# data_board.net
KiCad netlist of a schematic drawn in EAGLE
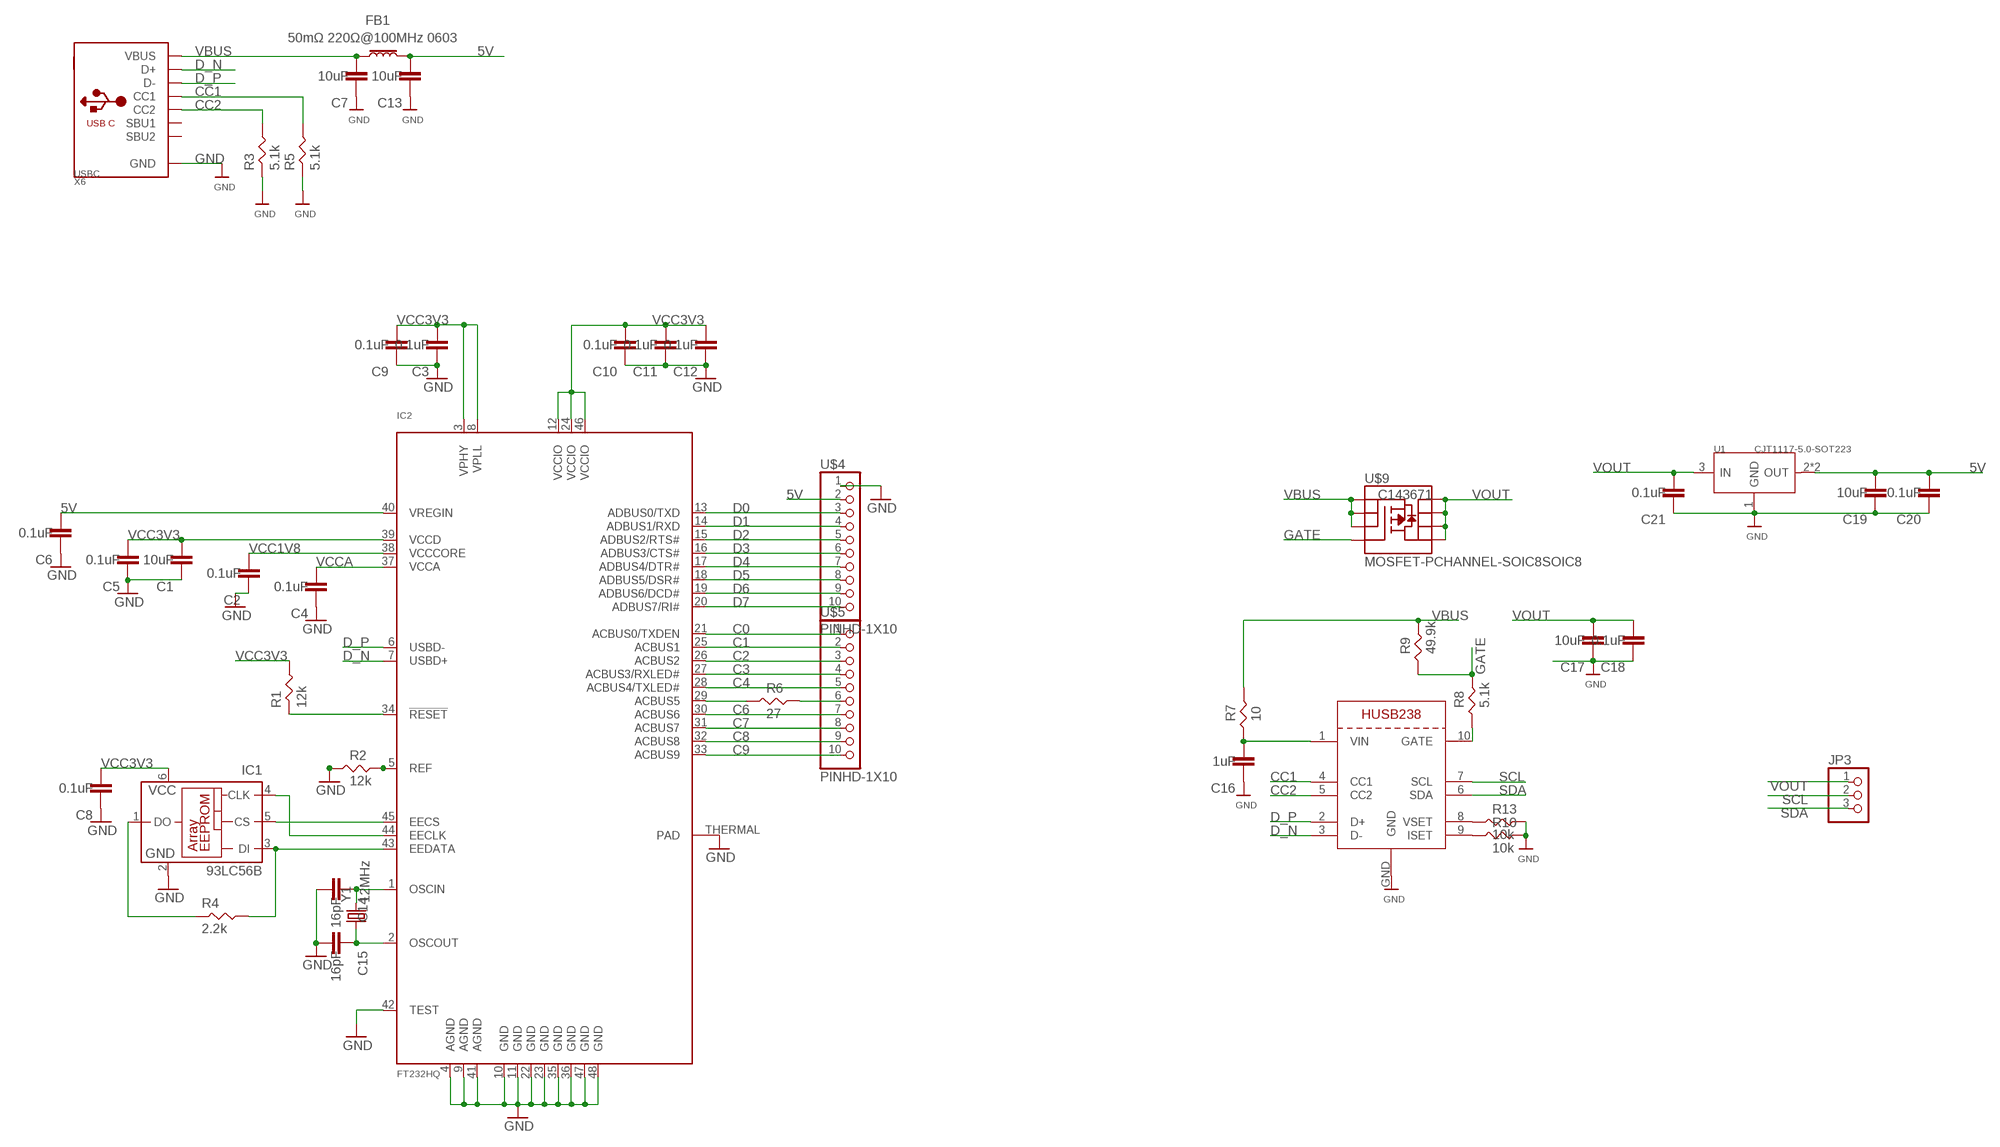
[diagram p0: schematic, sheet 1]

(export (version "E")
  (design (tool "Eeschema 10.0.6"))
  (components
    (comp (ref "C1")
      (value "10uF")
      (footprint "eagle-import:RESC0805_N")
      (libsource (lib "eagle-import") (part "CAPACITOR_0805_N"))
    )
    (comp (ref "C2")
      (value "0.1uF")
      (footprint "eagle-import:RESC0402_N")
      (libsource (lib "eagle-import") (part "CAPACITOR_0402_N"))
    )
    (comp (ref "C3")
      (value "0.1uF")
      (footprint "eagle-import:RESC0402_N")
      (libsource (lib "eagle-import") (part "CAPACITOR_0402_N"))
    )
    (comp (ref "C4")
      (value "0.1uF")
      (footprint "eagle-import:RESC0402_N")
      (libsource (lib "eagle-import") (part "CAPACITOR_0402_N"))
    )
    (comp (ref "C5")
      (value "0.1uF")
      (footprint "eagle-import:RESC0402_N")
      (libsource (lib "eagle-import") (part "CAPACITOR_0402_N"))
    )
    (comp (ref "C6")
      (value "0.1uF")
      (footprint "eagle-import:RESC0402_N")
      (libsource (lib "eagle-import") (part "CAPACITOR_0402_N"))
    )
    (comp (ref "C7")
      (value "10uF")
      (footprint "eagle-import:RESC0805_N")
      (libsource (lib "eagle-import") (part "CAPACITOR_0805_N"))
    )
    (comp (ref "C8")
      (value "0.1uF")
      (footprint "eagle-import:RESC0402_N")
      (libsource (lib "eagle-import") (part "CAPACITOR_0402_N"))
    )
    (comp (ref "C9")
      (value "0.1uF")
      (footprint "eagle-import:RESC0402_N")
      (libsource (lib "eagle-import") (part "CAPACITOR_0402_N"))
    )
    (comp (ref "C10")
      (value "0.1uF")
      (footprint "eagle-import:RESC0402_N")
      (libsource (lib "eagle-import") (part "CAPACITOR_0402_N"))
    )
    (comp (ref "C11")
      (value "0.1uF")
      (footprint "eagle-import:RESC0402_N")
      (libsource (lib "eagle-import") (part "CAPACITOR_0402_N"))
    )
    (comp (ref "C12")
      (value "0.1uF")
      (footprint "eagle-import:RESC0402_N")
      (libsource (lib "eagle-import") (part "CAPACITOR_0402_N"))
    )
    (comp (ref "C13")
      (value "10uF")
      (footprint "eagle-import:RESC0805_N")
      (libsource (lib "eagle-import") (part "CAPACITOR_0805_N"))
    )
    (comp (ref "C14")
      (value "16pF")
      (footprint "eagle-import:RESC0402_N")
      (libsource (lib "eagle-import") (part "CAPACITOR_0402_N"))
    )
    (comp (ref "C15")
      (value "16pF")
      (footprint "eagle-import:RESC0402_N")
      (libsource (lib "eagle-import") (part "CAPACITOR_0402_N"))
    )
    (comp (ref "C16")
      (value "1uF")
      (footprint "eagle-import:RESC0402_N")
      (libsource (lib "eagle-import") (part "CAPACITOR_0402_N"))
    )
    (comp (ref "C17")
      (value "10uF")
      (footprint "eagle-import:RESC0805_N")
      (libsource (lib "eagle-import") (part "CAPACITOR_0805_N"))
    )
    (comp (ref "C18")
      (value "0.1uF")
      (footprint "eagle-import:RESC0402_N")
      (libsource (lib "eagle-import") (part "CAPACITOR_0402_N"))
    )
    (comp (ref "C19")
      (value "10uF")
      (footprint "eagle-import:RESC0805_N")
      (libsource (lib "eagle-import") (part "CAPACITOR_0805_N"))
    )
    (comp (ref "C20")
      (value "0.1uF")
      (footprint "eagle-import:RESC0402_N")
      (libsource (lib "eagle-import") (part "CAPACITOR_0402_N"))
    )
    (comp (ref "C21")
      (value "0.1uF")
      (footprint "eagle-import:RESC0402_N")
      (libsource (lib "eagle-import") (part "CAPACITOR_0402_N"))
    )
    (comp (ref "FB1")
      (value "50mΩ 220Ω@100MHz 0603")
      (footprint "eagle-import:0603")
      (libsource (lib "eagle-import") (part "FERRITE_BEAD-0603"))
    )
    (comp (ref "IC1")
      (value "93LC56B")
      (footprint "eagle-import:SOT23-6")
      (fields (field (name "MF") "MICROCHIP") (field (name "MPN") "93LC76AT-I/OT"))
      (libsource (lib "eagle-import") (part "9376?ALC"))
    )
    (comp (ref "IC2")
      (value "FT232HQ")
      (footprint "eagle-import:QFN48_8MM")
      (libsource (lib "eagle-import") (part "FT232HQ"))
    )
    (comp (ref "JP3")
      (value "HEADER-1X3ROUND")
      (footprint "eagle-import:1X03_ROUND")
      (libsource (lib "eagle-import") (part "HEADER-1X3ROUND"))
    )
    (comp (ref "R1")
      (value "12k")
      (footprint "eagle-import:RES-0402")
      (libsource (lib "eagle-import") (part "RES-0402"))
    )
    (comp (ref "R2")
      (value "12k")
      (footprint "eagle-import:RES-0402")
      (libsource (lib "eagle-import") (part "RES-0402"))
    )
    (comp (ref "R3")
      (value "5.1k")
      (footprint "eagle-import:RES-0402")
      (libsource (lib "eagle-import") (part "RES-0402"))
    )
    (comp (ref "R4")
      (value "2.2k")
      (footprint "eagle-import:RES-0402")
      (libsource (lib "eagle-import") (part "RES-0402"))
    )
    (comp (ref "R5")
      (value "5.1k")
      (footprint "eagle-import:RES-0402")
      (libsource (lib "eagle-import") (part "RES-0402"))
    )
    (comp (ref "R6")
      (value "27")
      (footprint "eagle-import:RES-0402")
      (libsource (lib "eagle-import") (part "RES-0402"))
    )
    (comp (ref "R7")
      (value "10")
      (footprint "eagle-import:RES-0402")
      (libsource (lib "eagle-import") (part "RES-0402"))
    )
    (comp (ref "R8")
      (value "5.1k")
      (footprint "eagle-import:RES-0402")
      (libsource (lib "eagle-import") (part "RES-0402"))
    )
    (comp (ref "R9")
      (value "49.9k")
      (footprint "eagle-import:RES-0402")
      (libsource (lib "eagle-import") (part "RES-0402"))
    )
    (comp (ref "R10")
      (value "10k")
      (footprint "eagle-import:RES-0402")
      (libsource (lib "eagle-import") (part "RES-0402"))
    )
    (comp (ref "R13")
      (value "10k")
      (footprint "eagle-import:RES-0402")
      (libsource (lib "eagle-import") (part "RES-0402"))
    )
    (comp (ref "U$4")
      (value "PINHD-1X10")
      (footprint "eagle-import:1X10-BIG")
      (libsource (lib "eagle-import") (part "PINHD-1X10"))
    )
    (comp (ref "U$5")
      (value "PINHD-1X10")
      (footprint "eagle-import:1X10-BIG")
      (libsource (lib "eagle-import") (part "PINHD-1X10"))
    )
    (comp (ref "U$9")
      (value "MOSFET-PCHANNEL-SOIC8SOIC8")
      (footprint "eagle-import:SO08")
      (fields (field (name "LCSC") "C143671"))
      (libsource (lib "eagle-import") (part "MOSFET-PCHANNEL-SOIC8SOIC8"))
    )
    (comp (ref "U1")
      (value "CJT1117-5.0-SOT223")
      (footprint "eagle-import:SOT-223")
      (fields (field (name "MPN") "CJT1117-5.0"))
      (libsource (lib "eagle-import") (part "PMIC-CJT1117-5.0(SOT223)"))
    )
    (comp (ref "X3")
      (value "HUSB238")
      (footprint "eagle-import:DFN10_3X3MM")
      (libsource (lib "eagle-import") (part "HUSB238"))
    )
    (comp (ref "X6")
      (value "USBC")
      (footprint "eagle-import:USB_C_CUSB31-CFM2AX-01-X")
      (libsource (lib "eagle-import") (part "USB_C"))
    )
    (comp (ref "Y1")
      (value "12MHz")
      (footprint "eagle-import:CRYSTAL-SMD-5X3")
      (libsource (lib "eagle-import") (part "CRYSTALCRYSTAL-SMD-5X3-12MHZ"))
    )
  )
  (nets
    (net (code "1") (name "/5V") (class "Default")
      (node (ref "C13") (pin "2") (pinfunction "2_2") (pintype "passive"))
      (node (ref "C19") (pin "2") (pinfunction "2_2") (pintype "passive"))
      (node (ref "C20") (pin "2") (pinfunction "2_2") (pintype "passive"))
      (node (ref "C6") (pin "2") (pinfunction "2_2") (pintype "passive"))
      (node (ref "FB1") (pin "2") (pinfunction "2_2") (pintype "passive"))
      (node (ref "IC2") (pin "40") (pinfunction "VREGIN_40") (pintype "power_in"))
      (node (ref "U$4") (pin "2") (pinfunction "2_2") (pintype "passive"))
      (node (ref "U1") (pin "2") (pinfunction "OUT_2") (pintype "bidirectional"))
      (node (ref "U1") (pin "TER") (pinfunction "OUT_TER") (pintype "bidirectional"))
    )
    (net (code "2") (name "/C0") (class "Default")
      (node (ref "IC2") (pin "21") (pinfunction "ACBUS0/TXDEN_21") (pintype "bidirectional"))
      (node (ref "U$5") (pin "1") (pinfunction "1_1") (pintype "passive"))
    )
    (net (code "3") (name "/C1") (class "Default")
      (node (ref "IC2") (pin "25") (pinfunction "ACBUS1_25") (pintype "bidirectional"))
      (node (ref "U$5") (pin "2") (pinfunction "2_2") (pintype "passive"))
    )
    (net (code "4") (name "/C2") (class "Default")
      (node (ref "IC2") (pin "26") (pinfunction "ACBUS2_26") (pintype "bidirectional"))
      (node (ref "U$5") (pin "3") (pinfunction "3_3") (pintype "passive"))
    )
    (net (code "5") (name "/C3") (class "Default")
      (node (ref "IC2") (pin "27") (pinfunction "ACBUS3/RXLED#_27") (pintype "bidirectional"))
      (node (ref "U$5") (pin "4") (pinfunction "4_4") (pintype "passive"))
    )
    (net (code "6") (name "/C4") (class "Default")
      (node (ref "IC2") (pin "28") (pinfunction "ACBUS4/TXLED#_28") (pintype "bidirectional"))
      (node (ref "U$5") (pin "5") (pinfunction "5_5") (pintype "passive"))
    )
    (net (code "7") (name "/C6") (class "Default")
      (node (ref "IC2") (pin "30") (pinfunction "ACBUS6_30") (pintype "bidirectional"))
      (node (ref "U$5") (pin "7") (pinfunction "7_7") (pintype "passive"))
    )
    (net (code "8") (name "/C7") (class "Default")
      (node (ref "IC2") (pin "31") (pinfunction "ACBUS7_31") (pintype "bidirectional"))
      (node (ref "U$5") (pin "8") (pinfunction "8_8") (pintype "passive"))
    )
    (net (code "9") (name "/C8") (class "Default")
      (node (ref "IC2") (pin "32") (pinfunction "ACBUS8_32") (pintype "bidirectional"))
      (node (ref "U$5") (pin "9") (pinfunction "9_9") (pintype "passive"))
    )
    (net (code "10") (name "/C9") (class "Default")
      (node (ref "IC2") (pin "33") (pinfunction "ACBUS9_33") (pintype "bidirectional"))
      (node (ref "U$5") (pin "10") (pinfunction "10_10") (pintype "passive"))
    )
    (net (code "11") (name "/CC1") (class "Default")
      (node (ref "R5") (pin "P$2") (pinfunction "P$2_P$2") (pintype "bidirectional"))
      (node (ref "X3") (pin "4") (pinfunction "CC1_4") (pintype "input"))
      (node (ref "X6") (pin "A5") (pinfunction "CC1_A5") (pintype "bidirectional"))
    )
    (net (code "12") (name "/CC2") (class "Default")
      (node (ref "R3") (pin "P$2") (pinfunction "P$2_P$2") (pintype "bidirectional"))
      (node (ref "X3") (pin "5") (pinfunction "CC2_5") (pintype "input"))
      (node (ref "X6") (pin "B5") (pinfunction "CC2_B5") (pintype "bidirectional"))
    )
    (net (code "13") (name "/D0") (class "Default")
      (node (ref "IC2") (pin "13") (pinfunction "ADBUS0/TXD_13") (pintype "output"))
      (node (ref "U$4") (pin "3") (pinfunction "3_3") (pintype "passive"))
    )
    (net (code "14") (name "/D1") (class "Default")
      (node (ref "IC2") (pin "14") (pinfunction "ADBUS1/RXD_14") (pintype "input"))
      (node (ref "U$4") (pin "4") (pinfunction "4_4") (pintype "passive"))
    )
    (net (code "15") (name "/D2") (class "Default")
      (node (ref "IC2") (pin "15") (pinfunction "ADBUS2/RTS#_15") (pintype "output"))
      (node (ref "U$4") (pin "5") (pinfunction "5_5") (pintype "passive"))
    )
    (net (code "16") (name "/D3") (class "Default")
      (node (ref "IC2") (pin "16") (pinfunction "ADBUS3/CTS#_16") (pintype "input"))
      (node (ref "U$4") (pin "6") (pinfunction "6_6") (pintype "passive"))
    )
    (net (code "17") (name "/D4") (class "Default")
      (node (ref "IC2") (pin "17") (pinfunction "ADBUS4/DTR#_17") (pintype "output"))
      (node (ref "U$4") (pin "7") (pinfunction "7_7") (pintype "passive"))
    )
    (net (code "18") (name "/D5") (class "Default")
      (node (ref "IC2") (pin "18") (pinfunction "ADBUS5/DSR#_18") (pintype "input"))
      (node (ref "U$4") (pin "8") (pinfunction "8_8") (pintype "passive"))
    )
    (net (code "19") (name "/D6") (class "Default")
      (node (ref "IC2") (pin "19") (pinfunction "ADBUS6/DCD#_19") (pintype "input"))
      (node (ref "U$4") (pin "9") (pinfunction "9_9") (pintype "passive"))
    )
    (net (code "20") (name "/D7") (class "Default")
      (node (ref "IC2") (pin "20") (pinfunction "ADBUS7/RI#_20") (pintype "input"))
      (node (ref "U$4") (pin "10") (pinfunction "10_10") (pintype "passive"))
    )
    (net (code "21") (name "/D_N") (class "Default")
      (node (ref "IC2") (pin "7") (pinfunction "USBD+_7") (pintype "bidirectional"))
      (node (ref "X3") (pin "3") (pinfunction "D-_3") (pintype "input"))
      (node (ref "X6") (pin "A6") (pinfunction "D+_A6") (pintype "bidirectional"))
      (node (ref "X6") (pin "B6") (pinfunction "D+_B6") (pintype "bidirectional"))
    )
    (net (code "22") (name "/D_P") (class "Default")
      (node (ref "IC2") (pin "6") (pinfunction "USBD-_6") (pintype "bidirectional"))
      (node (ref "X3") (pin "2") (pinfunction "D+_2") (pintype "input"))
      (node (ref "X6") (pin "A7") (pinfunction "D-_A7") (pintype "bidirectional"))
      (node (ref "X6") (pin "B7") (pinfunction "D-_B7") (pintype "bidirectional"))
    )
    (net (code "23") (name "/GATE") (class "Default")
      (node (ref "R8") (pin "P$2") (pinfunction "P$2_P$2") (pintype "bidirectional"))
      (node (ref "R9") (pin "P$1") (pinfunction "P$1_P$1") (pintype "bidirectional"))
      (node (ref "U$9") (pin "4") (pinfunction "G_4") (pintype "bidirectional"))
    )
    (net (code "24") (name "/SCL") (class "Default")
      (node (ref "JP3") (pin "2") (pinfunction "2_2") (pintype "passive"))
      (node (ref "X3") (pin "7") (pinfunction "SCL_7") (pintype "bidirectional"))
    )
    (net (code "25") (name "/SDA") (class "Default")
      (node (ref "JP3") (pin "3") (pinfunction "3_3") (pintype "passive"))
      (node (ref "X3") (pin "6") (pinfunction "SDA_6") (pintype "bidirectional"))
    )
    (net (code "26") (name "/VBUS") (class "Default")
      (node (ref "C7") (pin "2") (pinfunction "2_2") (pintype "passive"))
      (node (ref "FB1") (pin "1") (pinfunction "1_1") (pintype "passive"))
      (node (ref "R7") (pin "P$2") (pinfunction "P$2_P$2") (pintype "bidirectional"))
      (node (ref "R9") (pin "P$2") (pinfunction "P$2_P$2") (pintype "bidirectional"))
      (node (ref "U$9") (pin "1") (pinfunction "S_1") (pintype "bidirectional"))
      (node (ref "U$9") (pin "2") (pinfunction "S_2") (pintype "bidirectional"))
      (node (ref "U$9") (pin "3") (pinfunction "S_3") (pintype "bidirectional"))
      (node (ref "X6") (pin "A4B9") (pinfunction "VBUS_A4B9") (pintype "power_in"))
      (node (ref "X6") (pin "B4A9") (pinfunction "VBUS_B4A9") (pintype "power_in"))
    )
    (net (code "27") (name "/VCC1V8") (class "Default")
      (node (ref "C2") (pin "2") (pinfunction "2_2") (pintype "passive"))
      (node (ref "IC2") (pin "38") (pinfunction "VCCCORE_38") (pintype "power_in"))
    )
    (net (code "28") (name "/VCC3V3") (class "Default")
      (node (ref "C1") (pin "2") (pinfunction "2_2") (pintype "passive"))
      (node (ref "C10") (pin "2") (pinfunction "2_2") (pintype "passive"))
      (node (ref "C11") (pin "2") (pinfunction "2_2") (pintype "passive"))
      (node (ref "C12") (pin "2") (pinfunction "2_2") (pintype "passive"))
      (node (ref "C3") (pin "2") (pinfunction "2_2") (pintype "passive"))
      (node (ref "C5") (pin "2") (pinfunction "2_2") (pintype "passive"))
      (node (ref "C8") (pin "2") (pinfunction "2_2") (pintype "passive"))
      (node (ref "C9") (pin "2") (pinfunction "2_2") (pintype "passive"))
      (node (ref "IC1") (pin "6") (pinfunction "VCC_6") (pintype "power_in"))
      (node (ref "IC2") (pin "12") (pinfunction "VCCIO_12") (pintype "power_in"))
      (node (ref "IC2") (pin "24") (pinfunction "VCCIO_24") (pintype "power_in"))
      (node (ref "IC2") (pin "3") (pinfunction "VPHY_3") (pintype "power_in"))
      (node (ref "IC2") (pin "39") (pinfunction "VCCD_39") (pintype "power_in"))
      (node (ref "IC2") (pin "46") (pinfunction "VCCIO_46") (pintype "power_in"))
      (node (ref "IC2") (pin "8") (pinfunction "VPLL_8") (pintype "power_in"))
      (node (ref "R1") (pin "P$2") (pinfunction "P$2_P$2") (pintype "bidirectional"))
    )
    (net (code "29") (name "/VCCA") (class "Default")
      (node (ref "C4") (pin "2") (pinfunction "2_2") (pintype "passive"))
      (node (ref "IC2") (pin "37") (pinfunction "VCCA_37") (pintype "power_in"))
    )
    (net (code "30") (name "/VOUT") (class "Default")
      (node (ref "C17") (pin "2") (pinfunction "2_2") (pintype "passive"))
      (node (ref "C18") (pin "2") (pinfunction "2_2") (pintype "passive"))
      (node (ref "C21") (pin "2") (pinfunction "2_2") (pintype "passive"))
      (node (ref "JP3") (pin "1") (pinfunction "1_1") (pintype "passive"))
      (node (ref "U$9") (pin "5") (pinfunction "D_5") (pintype "bidirectional"))
      (node (ref "U$9") (pin "6") (pinfunction "D_6") (pintype "bidirectional"))
      (node (ref "U$9") (pin "7") (pinfunction "D_7") (pintype "bidirectional"))
      (node (ref "U$9") (pin "8") (pinfunction "D_8") (pintype "bidirectional"))
      (node (ref "U1") (pin "3") (pinfunction "IN_3") (pintype "bidirectional"))
    )
    (net (code "31") (name "GND") (class "Default")
      (node (ref "C1") (pin "1") (pinfunction "1_1") (pintype "passive"))
      (node (ref "C10") (pin "1") (pinfunction "1_1") (pintype "passive"))
      (node (ref "C11") (pin "1") (pinfunction "1_1") (pintype "passive"))
      (node (ref "C12") (pin "1") (pinfunction "1_1") (pintype "passive"))
      (node (ref "C13") (pin "1") (pinfunction "1_1") (pintype "passive"))
      (node (ref "C14") (pin "2") (pinfunction "2_2") (pintype "passive"))
      (node (ref "C15") (pin "2") (pinfunction "2_2") (pintype "passive"))
      (node (ref "C16") (pin "1") (pinfunction "1_1") (pintype "passive"))
      (node (ref "C17") (pin "1") (pinfunction "1_1") (pintype "passive"))
      (node (ref "C18") (pin "1") (pinfunction "1_1") (pintype "passive"))
      (node (ref "C19") (pin "1") (pinfunction "1_1") (pintype "passive"))
      (node (ref "C2") (pin "1") (pinfunction "1_1") (pintype "passive"))
      (node (ref "C20") (pin "1") (pinfunction "1_1") (pintype "passive"))
      (node (ref "C21") (pin "1") (pinfunction "1_1") (pintype "passive"))
      (node (ref "C3") (pin "1") (pinfunction "1_1") (pintype "passive"))
      (node (ref "C4") (pin "1") (pinfunction "1_1") (pintype "passive"))
      (node (ref "C5") (pin "1") (pinfunction "1_1") (pintype "passive"))
      (node (ref "C6") (pin "1") (pinfunction "1_1") (pintype "passive"))
      (node (ref "C7") (pin "1") (pinfunction "1_1") (pintype "passive"))
      (node (ref "C8") (pin "1") (pinfunction "1_1") (pintype "passive"))
      (node (ref "C9") (pin "1") (pinfunction "1_1") (pintype "passive"))
      (node (ref "IC1") (pin "2") (pinfunction "GND_2") (pintype "power_in"))
      (node (ref "IC2") (pin "10") (pinfunction "GND_10") (pintype "power_in"))
      (node (ref "IC2") (pin "11") (pinfunction "GND_11") (pintype "power_in"))
      (node (ref "IC2") (pin "22") (pinfunction "GND_22") (pintype "power_in"))
      (node (ref "IC2") (pin "23") (pinfunction "GND_23") (pintype "power_in"))
      (node (ref "IC2") (pin "35") (pinfunction "GND_35") (pintype "power_in"))
      (node (ref "IC2") (pin "36") (pinfunction "GND_36") (pintype "power_in"))
      (node (ref "IC2") (pin "4") (pinfunction "AGND_4") (pintype "power_in"))
      (node (ref "IC2") (pin "41") (pinfunction "AGND_41") (pintype "power_in"))
      (node (ref "IC2") (pin "42") (pinfunction "TEST_42") (pintype "input"))
      (node (ref "IC2") (pin "47") (pinfunction "GND_47") (pintype "power_in"))
      (node (ref "IC2") (pin "48") (pinfunction "GND_48") (pintype "power_in"))
      (node (ref "IC2") (pin "9") (pinfunction "AGND_9") (pintype "power_in"))
      (node (ref "IC2") (pin "THERMAL") (pinfunction "PAD_THERMAL") (pintype "passive"))
      (node (ref "R10") (pin "P$2") (pinfunction "P$2_P$2") (pintype "bidirectional"))
      (node (ref "R13") (pin "P$2") (pinfunction "P$2_P$2") (pintype "bidirectional"))
      (node (ref "R2") (pin "P$1") (pinfunction "P$1_P$1") (pintype "bidirectional"))
      (node (ref "R3") (pin "P$1") (pinfunction "P$1_P$1") (pintype "bidirectional"))
      (node (ref "R5") (pin "P$1") (pinfunction "P$1_P$1") (pintype "bidirectional"))
      (node (ref "U$4") (pin "1") (pinfunction "1_1") (pintype "passive"))
      (node (ref "U1") (pin "1") (pinfunction "GND_1") (pintype "bidirectional"))
      (node (ref "X3") (pin "GND") (pinfunction "GND_GND") (pintype "power_in"))
      (node (ref "X6") (pin "A1B12") (pinfunction "GND_A1B12") (pintype "power_in"))
      (node (ref "X6") (pin "B1A12") (pinfunction "GND_B1A12") (pintype "power_in"))
    )
    (net (code "32") (name "Net-(IC1-CLK)") (class "Default")
      (node (ref "IC1") (pin "4") (pinfunction "CLK_4") (pintype "input"))
      (node (ref "IC2") (pin "44") (pinfunction "EECLK_44") (pintype "output"))
    )
    (net (code "33") (name "Net-(IC1-CS)") (class "Default")
      (node (ref "IC1") (pin "5") (pinfunction "CS_5") (pintype "input"))
      (node (ref "IC2") (pin "45") (pinfunction "EECS_45") (pintype "bidirectional"))
    )
    (net (code "34") (name "Net-(IC1-DI)") (class "Default")
      (node (ref "IC1") (pin "3") (pinfunction "DI_3") (pintype "input"))
      (node (ref "IC2") (pin "43") (pinfunction "EEDATA_43") (pintype "bidirectional"))
      (node (ref "R4") (pin "P$2") (pinfunction "P$2_P$2") (pintype "bidirectional"))
    )
    (net (code "35") (name "Net-(IC1-DO)") (class "Default")
      (node (ref "IC1") (pin "1") (pinfunction "DO_1") (pintype "tri_state"))
      (node (ref "R4") (pin "P$1") (pinfunction "P$1_P$1") (pintype "bidirectional"))
    )
    (net (code "36") (name "Net-(IC2-ACBUS5)") (class "Default")
      (node (ref "IC2") (pin "29") (pinfunction "ACBUS5_29") (pintype "bidirectional"))
      (node (ref "R6") (pin "P$1") (pinfunction "P$1_P$1") (pintype "bidirectional"))
    )
    (net (code "37") (name "Net-(IC2-OSCIN)") (class "Default")
      (node (ref "C14") (pin "1") (pinfunction "1_1") (pintype "passive"))
      (node (ref "IC2") (pin "1") (pinfunction "OSCIN_1") (pintype "input"))
      (node (ref "Y1") (pin "3") (pinfunction "2_3") (pintype "passive"))
    )
    (net (code "38") (name "Net-(IC2-OSCOUT)") (class "Default")
      (node (ref "C15") (pin "1") (pinfunction "1_1") (pintype "passive"))
      (node (ref "IC2") (pin "2") (pinfunction "OSCOUT_2") (pintype "output"))
      (node (ref "Y1") (pin "1") (pinfunction "1_1") (pintype "passive"))
    )
    (net (code "39") (name "Net-(IC2-REF)") (class "Default")
      (node (ref "IC2") (pin "5") (pinfunction "REF_5") (pintype "input"))
      (node (ref "R2") (pin "P$2") (pinfunction "P$2_P$2") (pintype "bidirectional"))
    )
    (net (code "40") (name "Net-(IC2-~{RESET})") (class "Default")
      (node (ref "IC2") (pin "34") (pinfunction "~{RESET}_34") (pintype "input"))
      (node (ref "R1") (pin "P$1") (pinfunction "P$1_P$1") (pintype "bidirectional"))
    )
    (net (code "41") (name "Net-(R6-PadP$2)") (class "Default")
      (node (ref "R6") (pin "P$2") (pinfunction "P$2_P$2") (pintype "bidirectional"))
      (node (ref "U$5") (pin "6") (pinfunction "6_6") (pintype "passive"))
    )
    (net (code "42") (name "Net-(X3-GATE)") (class "Default")
      (node (ref "R8") (pin "P$1") (pinfunction "P$1_P$1") (pintype "bidirectional"))
      (node (ref "X3") (pin "10") (pinfunction "GATE_10") (pintype "output"))
    )
    (net (code "43") (name "Net-(X3-ISET)") (class "Default")
      (node (ref "R10") (pin "P$1") (pinfunction "P$1_P$1") (pintype "bidirectional"))
      (node (ref "X3") (pin "9") (pinfunction "ISET_9") (pintype "passive"))
    )
    (net (code "44") (name "Net-(X3-VIN)") (class "Default")
      (node (ref "C16") (pin "2") (pinfunction "2_2") (pintype "passive"))
      (node (ref "R7") (pin "P$1") (pinfunction "P$1_P$1") (pintype "bidirectional"))
      (node (ref "X3") (pin "1") (pinfunction "VIN_1") (pintype "power_in"))
    )
    (net (code "45") (name "Net-(X3-VSET)") (class "Default")
      (node (ref "R13") (pin "P$1") (pinfunction "P$1_P$1") (pintype "bidirectional"))
      (node (ref "X3") (pin "8") (pinfunction "VSET_8") (pintype "passive"))
    )
    (net (code "46") (name "unconnected-(X6-SBU1-PadA8)") (class "Default")
      (node (ref "X6") (pin "A8") (pinfunction "SBU1_A8") (pintype "bidirectional"))
    )
    (net (code "47") (name "unconnected-(X6-SBU2-PadB8)") (class "Default")
      (node (ref "X6") (pin "B8") (pinfunction "SBU2_B8") (pintype "bidirectional"))
    )
  )
)
